# S7CAS-PLEIADES-CARTE-MERE_P01_IO.net
KiCad netlist of a schematic drawn in Altium Designer
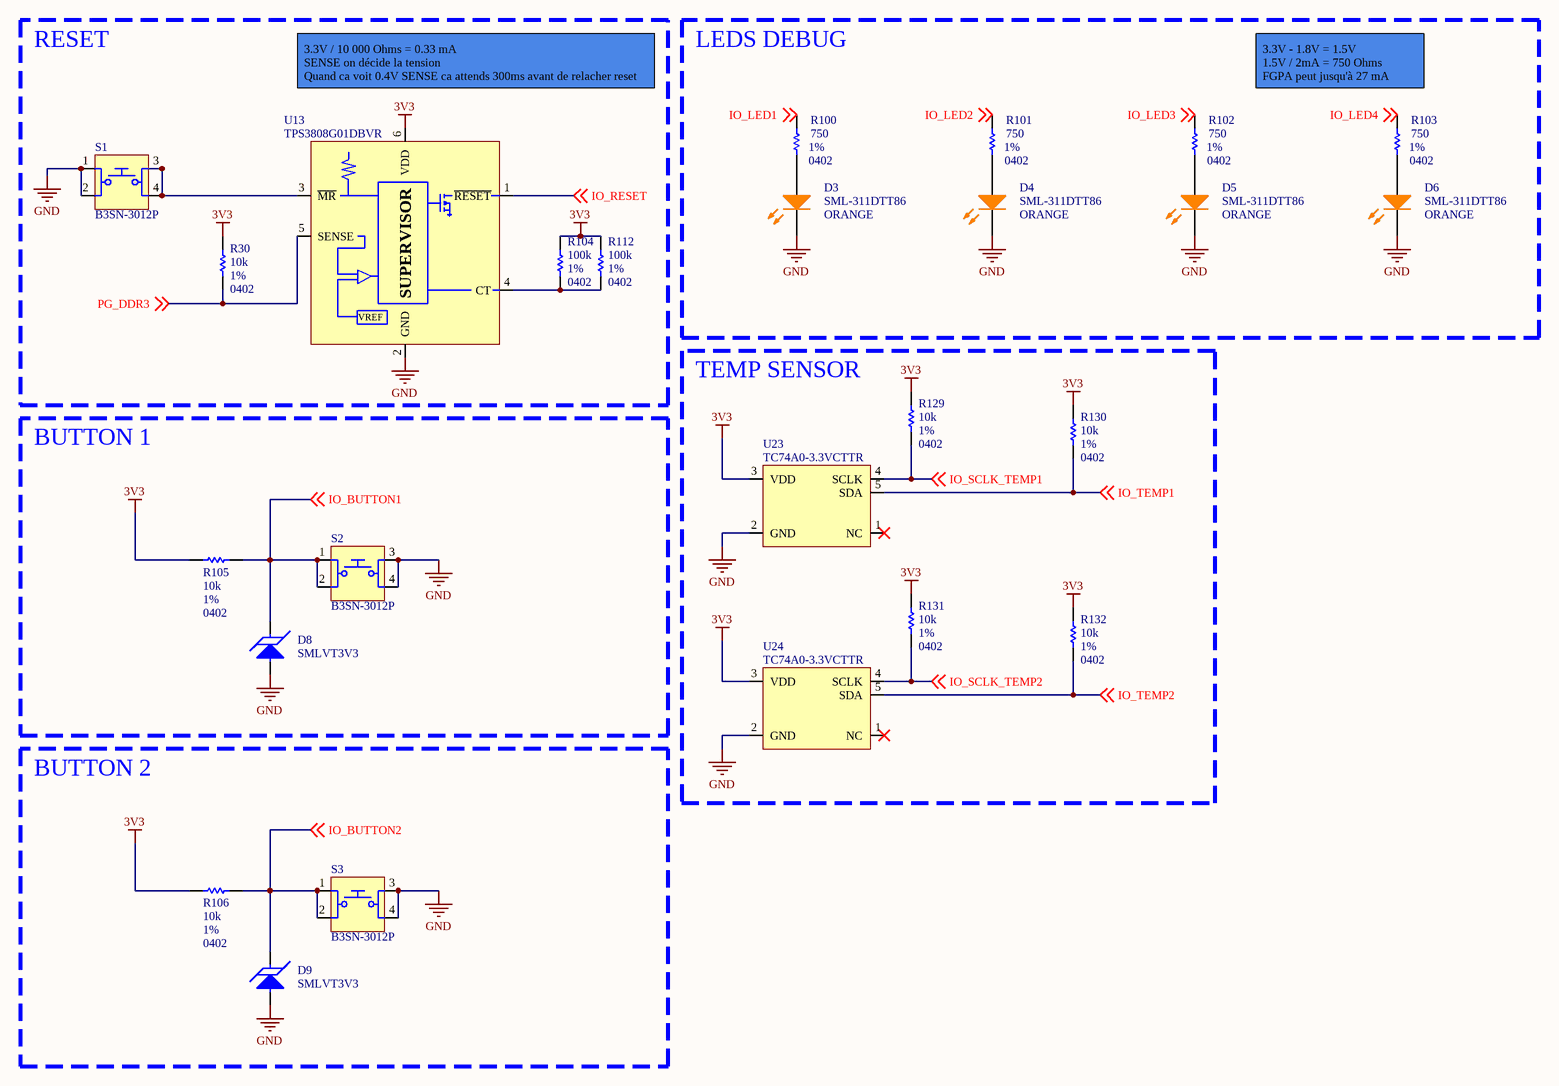
[diagram p0: S7CAS-PLEIADES-CARTE-MERE_P01_IO.SchDoc]

(export (version "E")
  (design (tool "Eeschema 10.0.6"))
  (components
    (comp (ref "D3")
      (value "SML-311DTT86")
      (footprint "LED_0603")
      (description "LED - 611nM ORANGE 2mA - 0603")
      (fields
        (field (name "VOLTAGE") "1.8V")
        (field (name "MFG") "ROHM Semiconductor")
        (field (name "ALTIUM_VALUE") "ORANGE")
        (field (name "CREATEDBY") "Jonathan Bouchard")
      )
      (libsource (lib "s7cas_lib2023") (part "LED_SML-311DTT86"))
    )
    (comp (ref "D4")
      (value "SML-311DTT86")
      (footprint "LED_0603")
      (description "LED - 611nM ORANGE 2mA - 0603")
      (fields
        (field (name "VOLTAGE") "1.8V")
        (field (name "MFG") "ROHM Semiconductor")
        (field (name "ALTIUM_VALUE") "ORANGE")
        (field (name "CREATEDBY") "Jonathan Bouchard")
      )
      (libsource (lib "s7cas_lib2023") (part "LED_SML-311DTT86"))
    )
    (comp (ref "D5")
      (value "SML-311DTT86")
      (footprint "LED_0603")
      (description "LED - 611nM ORANGE 2mA - 0603")
      (fields
        (field (name "VOLTAGE") "1.8V")
        (field (name "MFG") "ROHM Semiconductor")
        (field (name "ALTIUM_VALUE") "ORANGE")
        (field (name "CREATEDBY") "Jonathan Bouchard")
      )
      (libsource (lib "s7cas_lib2023") (part "LED_SML-311DTT86"))
    )
    (comp (ref "D6")
      (value "SML-311DTT86")
      (footprint "LED_0603")
      (description "LED - 611nM ORANGE 2mA - 0603")
      (fields
        (field (name "VOLTAGE") "1.8V")
        (field (name "MFG") "ROHM Semiconductor")
        (field (name "ALTIUM_VALUE") "ORANGE")
        (field (name "CREATEDBY") "Jonathan Bouchard")
      )
      (libsource (lib "s7cas_lib2023") (part "LED_SML-311DTT86"))
    )
    (comp (ref "D8")
      (value "SMLVT3V3")
      (footprint "TVS_POW_SMLVT3V3")
      (description "TVS - 3.3V 10.3V 600W - DO214AA")
      (fields
        (field (name "CREATEDBY/DATE") "Jonathan Bouchard - 2019-04-27")
        (field (name "VERIFIEDBY") "Nicolas V. (2019-05-06)")
      )
      (libsource (lib "s7cas_lib2023") (part "TVS_POW_SMLVT3V3"))
    )
    (comp (ref "D9")
      (value "SMLVT3V3")
      (footprint "TVS_POW_SMLVT3V3")
      (description "TVS - 3.3V 10.3V 600W - DO214AA")
      (fields
        (field (name "CREATEDBY/DATE") "Jonathan Bouchard - 2019-04-27")
        (field (name "VERIFIEDBY") "Nicolas V. (2019-05-06)")
      )
      (libsource (lib "s7cas_lib2023") (part "TVS_POW_SMLVT3V3"))
    )
    (comp (ref "R30")
      (value "10k")
      (footprint "RES_0402")
      (description "10 kOhms ±1% 0.063W, 1/16W Chip Resistor 0402 (1005 Metric) Automotive AEC-Q200 Thick Film")
      (fields
        (field (name "VOLTAGE") "75V")
        (field (name "MFG PART NUMBER") "RMCF0402FT10K0")
        (field (name "PACKAGE") "0402")
        (field (name "PRECISION") "1%")
        (field (name "CREATEDBY") "Jonathan Bouchard")
      )
      (libsource (lib "s7cas_lib2023") (part "RES - 0402"))
    )
    (comp (ref "R100")
      (value "750")
      (footprint "RES_0402")
      (description "750 Ohms ±0.1% 0.063W, 1/16W Chip Resistor 0402 (1005 Metric) Automotive AEC-Q200 Thin Film")
      (fields
        (field (name "VOLTAGE") "50V")
        (field (name "MFG") "Panasonic Electronic Components")
        (field (name "PACKAGE") "0402")
        (field (name "PRECISION") "1%")
        (field (name "CREATEDBY") "Jonathan Bouchard")
      )
      (libsource (lib "s7cas_lib2023") (part "RES - 0402"))
    )
    (comp (ref "R101")
      (value "750")
      (footprint "RES_0402")
      (description "750 Ohms ±0.1% 0.063W, 1/16W Chip Resistor 0402 (1005 Metric) Automotive AEC-Q200 Thin Film")
      (fields
        (field (name "VOLTAGE") "50V")
        (field (name "MFG") "Panasonic Electronic Components")
        (field (name "PACKAGE") "0402")
        (field (name "PRECISION") "1%")
        (field (name "CREATEDBY") "Jonathan Bouchard")
      )
      (libsource (lib "s7cas_lib2023") (part "RES - 0402"))
    )
    (comp (ref "R102")
      (value "750")
      (footprint "RES_0402")
      (description "750 Ohms ±0.1% 0.063W, 1/16W Chip Resistor 0402 (1005 Metric) Automotive AEC-Q200 Thin Film")
      (fields
        (field (name "VOLTAGE") "50V")
        (field (name "MFG") "Panasonic Electronic Components")
        (field (name "PACKAGE") "0402")
        (field (name "PRECISION") "1%")
        (field (name "CREATEDBY") "Jonathan Bouchard")
      )
      (libsource (lib "s7cas_lib2023") (part "RES - 0402"))
    )
    (comp (ref "R103")
      (value "750")
      (footprint "RES_0402")
      (description "750 Ohms ±0.1% 0.063W, 1/16W Chip Resistor 0402 (1005 Metric) Automotive AEC-Q200 Thin Film")
      (fields
        (field (name "VOLTAGE") "50V")
        (field (name "MFG") "Panasonic Electronic Components")
        (field (name "PACKAGE") "0402")
        (field (name "PRECISION") "1%")
        (field (name "CREATEDBY") "Jonathan Bouchard")
      )
      (libsource (lib "s7cas_lib2023") (part "RES - 0402"))
    )
    (comp (ref "R104")
      (value "100k")
      (footprint "RES_0402")
      (description "100 kOhms ±1% 0.063W, 1/16W Chip Resistor 0402 (1005 Metric) Moisture Resistant Thick Film")
      (fields
        (field (name "VOLTAGE") "75V")
        (field (name "MFG PART NUMBER") "RC0402FR-07100KL")
        (field (name "PACKAGE") "0402")
        (field (name "PRECISION") "1%")
        (field (name "CREATEDBY") "Jonathan Bouchard")
      )
      (libsource (lib "s7cas_lib2023") (part "RES - 0402"))
    )
    (comp (ref "R105")
      (value "10k")
      (footprint "RES_0402")
      (description "10 kOhms ±1% 0.063W, 1/16W Chip Resistor 0402 (1005 Metric) Automotive AEC-Q200 Thick Film")
      (fields
        (field (name "VOLTAGE") "75V")
        (field (name "MFG PART NUMBER") "RMCF0402FT10K0")
        (field (name "PACKAGE") "0402")
        (field (name "PRECISION") "1%")
        (field (name "CREATEDBY") "Jonathan Bouchard")
      )
      (libsource (lib "s7cas_lib2023") (part "RES - 0402"))
    )
    (comp (ref "R106")
      (value "10k")
      (footprint "RES_0402")
      (description "10 kOhms ±1% 0.063W, 1/16W Chip Resistor 0402 (1005 Metric) Automotive AEC-Q200 Thick Film")
      (fields
        (field (name "VOLTAGE") "75V")
        (field (name "MFG PART NUMBER") "RMCF0402FT10K0")
        (field (name "PACKAGE") "0402")
        (field (name "PRECISION") "1%")
        (field (name "CREATEDBY") "Jonathan Bouchard")
      )
      (libsource (lib "s7cas_lib2023") (part "RES - 0402"))
    )
    (comp (ref "R112")
      (value "100k")
      (footprint "RES_0402")
      (description "100 kOhms ±1% 0.063W, 1/16W Chip Resistor 0402 (1005 Metric) Moisture Resistant Thick Film")
      (fields
        (field (name "VOLTAGE") "75V")
        (field (name "MFG PART NUMBER") "RC0402FR-07100KL")
        (field (name "PACKAGE") "0402")
        (field (name "PRECISION") "1%")
        (field (name "CREATEDBY") "Jonathan Bouchard")
      )
      (libsource (lib "s7cas_lib2023") (part "RES - 0402"))
    )
    (comp (ref "R129")
      (value "10k")
      (footprint "RES_0402")
      (description "10 kOhms ±1% 0.063W, 1/16W Chip Resistor 0402 (1005 Metric) Automotive AEC-Q200 Thick Film")
      (fields
        (field (name "VOLTAGE") "75V")
        (field (name "MFG PART NUMBER") "RMCF0402FT10K0")
        (field (name "PACKAGE") "0402")
        (field (name "PRECISION") "1%")
        (field (name "CREATEDBY") "Jonathan Bouchard")
      )
      (libsource (lib "s7cas_lib2023") (part "RES - 0402"))
    )
    (comp (ref "R130")
      (value "10k")
      (footprint "RES_0402")
      (description "10 kOhms ±1% 0.063W, 1/16W Chip Resistor 0402 (1005 Metric) Automotive AEC-Q200 Thick Film")
      (fields
        (field (name "VOLTAGE") "75V")
        (field (name "MFG PART NUMBER") "RMCF0402FT10K0")
        (field (name "PACKAGE") "0402")
        (field (name "PRECISION") "1%")
        (field (name "CREATEDBY") "Jonathan Bouchard")
      )
      (libsource (lib "s7cas_lib2023") (part "RES - 0402"))
    )
    (comp (ref "R131")
      (value "10k")
      (footprint "RES_0402")
      (description "10 kOhms ±1% 0.063W, 1/16W Chip Resistor 0402 (1005 Metric) Automotive AEC-Q200 Thick Film")
      (fields
        (field (name "VOLTAGE") "75V")
        (field (name "MFG PART NUMBER") "RMCF0402FT10K0")
        (field (name "PACKAGE") "0402")
        (field (name "PRECISION") "1%")
        (field (name "CREATEDBY") "Jonathan Bouchard")
      )
      (libsource (lib "s7cas_lib2023") (part "RES - 0402"))
    )
    (comp (ref "R132")
      (value "10k")
      (footprint "RES_0402")
      (description "10 kOhms ±1% 0.063W, 1/16W Chip Resistor 0402 (1005 Metric) Automotive AEC-Q200 Thick Film")
      (fields
        (field (name "VOLTAGE") "75V")
        (field (name "MFG PART NUMBER") "RMCF0402FT10K0")
        (field (name "PACKAGE") "0402")
        (field (name "PRECISION") "1%")
        (field (name "CREATEDBY") "Jonathan Bouchard")
      )
      (libsource (lib "s7cas_lib2023") (part "RES - 0402"))
    )
    (comp (ref "S1")
      (value "B3SN-3012P")
      (footprint "SWI_TACT_B3SN-3012P")
      (description "SWI - SWITCH TACTILE SPST-NO 0.05A 24V -SMD")
      (fields
        (field (name "CREATEDBY/DATE") "Olivier Bernard / 5/12/2017")
        (field (name "VERIFIEDBY") "Caroline Paulin / 11 juillet 2018")
      )
      (libsource (lib "s7cas_lib2023") (part "SWI_TACT_B3SN-3012P_1"))
    )
    (comp (ref "S2")
      (value "B3SN-3012P")
      (footprint "SWI_TACT_B3SN-3012P")
      (description "SWI - SWITCH TACTILE SPST-NO 0.05A 24V -SMD")
      (fields
        (field (name "CREATEDBY/DATE") "Olivier Bernard / 5/12/2017")
        (field (name "VERIFIEDBY") "Caroline Paulin / 11 juillet 2018")
      )
      (libsource (lib "s7cas_lib2023") (part "SWI_TACT_B3SN-3012P_1"))
    )
    (comp (ref "S3")
      (value "B3SN-3012P")
      (footprint "SWI_TACT_B3SN-3012P")
      (description "SWI - SWITCH TACTILE SPST-NO 0.05A 24V -SMD")
      (fields
        (field (name "CREATEDBY/DATE") "Olivier Bernard / 5/12/2017")
        (field (name "VERIFIEDBY") "Caroline Paulin / 11 juillet 2018")
      )
      (libsource (lib "s7cas_lib2023") (part "SWI_TACT_B3SN-3012P_1"))
    )
    (comp (ref "U13")
      (value "TPS3808G01DBVR")
      (footprint "POW_RESET_TPS3808")
      (description "POW - VOLT SUPERVISOR ADJ - SOT23-6")
      (fields (field (name "MFG") "Texas Instruments") (field (name "CREATEDBY") "Jonathan Bouchard"))
      (libsource (lib "s7cas_lib2023") (part "POW_RESET_TPS3808G01DBVR"))
    )
    (comp (ref "U23")
      (value "TC74A0-3.3VCTTR")
      (footprint "SEN_TEMP_TC74A0-3.3VCTTR")
      (description "SENS - TEMPERATURE SENSOR I2C/SMBUS - SOT23-5")
      (fields
        (field (name "VOLTAGE") "2.7 V ~ 5.5 V")
        (field (name "MFG") "Microchip")
        (field (name "CREATEDBY") "Jonathan Bouchard")
      )
      (libsource (lib "s7cas_lib2023") (part "SENS_TEMP_TC74A0-3.3VCTTR"))
    )
    (comp (ref "U24")
      (value "TC74A0-3.3VCTTR")
      (footprint "SEN_TEMP_TC74A0-3.3VCTTR")
      (description "SENS - TEMPERATURE SENSOR I2C/SMBUS - SOT23-5")
      (fields
        (field (name "VOLTAGE") "2.7 V ~ 5.5 V")
        (field (name "MFG") "Microchip")
        (field (name "CREATEDBY") "Jonathan Bouchard")
      )
      (libsource (lib "s7cas_lib2023") (part "SENS_TEMP_TC74A0-3.3VCTTR"))
    )
  )
  (nets
    (net (code "1") (name "3V3") (class "Default")
      (node (ref "R104") (pin "2") (pinfunction "2_2") (pintype "passive"))
      (node (ref "R105") (pin "1") (pinfunction "1_1") (pintype "passive"))
      (node (ref "R106") (pin "1") (pinfunction "1_1") (pintype "passive"))
      (node (ref "R112") (pin "2") (pinfunction "2_2") (pintype "passive"))
      (node (ref "R129") (pin "2") (pinfunction "2_2") (pintype "passive"))
      (node (ref "R130") (pin "2") (pinfunction "2_2") (pintype "passive"))
      (node (ref "R131") (pin "2") (pinfunction "2_2") (pintype "passive"))
      (node (ref "R132") (pin "2") (pinfunction "2_2") (pintype "passive"))
      (node (ref "R30") (pin "2") (pinfunction "2_2") (pintype "passive"))
      (node (ref "U13") (pin "6") (pinfunction "VDD_6") (pintype "power_in"))
      (node (ref "U23") (pin "3") (pinfunction "VDD_3") (pintype "passive"))
      (node (ref "U24") (pin "3") (pinfunction "VDD_3") (pintype "passive"))
    )
    (net (code "2") (name "GND") (class "Default")
      (node (ref "D3") (pin "K") (pinfunction "K_K") (pintype "passive"))
      (node (ref "D4") (pin "K") (pinfunction "K_K") (pintype "passive"))
      (node (ref "D5") (pin "K") (pinfunction "K_K") (pintype "passive"))
      (node (ref "D6") (pin "K") (pinfunction "K_K") (pintype "passive"))
      (node (ref "D8") (pin "A") (pinfunction "A_A") (pintype "passive"))
      (node (ref "D9") (pin "A") (pinfunction "A_A") (pintype "passive"))
      (node (ref "S1") (pin "1") (pinfunction "1_1") (pintype "passive"))
      (node (ref "S1") (pin "2") (pinfunction "2_2") (pintype "passive"))
      (node (ref "S2") (pin "3") (pinfunction "3_3") (pintype "passive"))
      (node (ref "S2") (pin "4") (pinfunction "4_4") (pintype "passive"))
      (node (ref "S3") (pin "3") (pinfunction "3_3") (pintype "passive"))
      (node (ref "S3") (pin "4") (pinfunction "4_4") (pintype "passive"))
      (node (ref "U13") (pin "2") (pinfunction "GND_2") (pintype "passive"))
      (node (ref "U23") (pin "2") (pinfunction "GND_2") (pintype "passive"))
      (node (ref "U24") (pin "2") (pinfunction "GND_2") (pintype "passive"))
    )
    (net (code "3") (name "IO_BUTTON1") (class "Default")
      (node (ref "D8") (pin "K") (pinfunction "K_K") (pintype "passive"))
      (node (ref "R105") (pin "2") (pinfunction "2_2") (pintype "passive"))
      (node (ref "S2") (pin "1") (pinfunction "1_1") (pintype "passive"))
      (node (ref "S2") (pin "2") (pinfunction "2_2") (pintype "passive"))
    )
    (net (code "4") (name "IO_BUTTON2") (class "Default")
      (node (ref "D9") (pin "K") (pinfunction "K_K") (pintype "passive"))
      (node (ref "R106") (pin "2") (pinfunction "2_2") (pintype "passive"))
      (node (ref "S3") (pin "1") (pinfunction "1_1") (pintype "passive"))
      (node (ref "S3") (pin "2") (pinfunction "2_2") (pintype "passive"))
    )
    (net (code "5") (name "IO_LED1") (class "Default")
      (node (ref "R100") (pin "2") (pinfunction "2_2") (pintype "passive"))
    )
    (net (code "6") (name "IO_LED2") (class "Default")
      (node (ref "R101") (pin "2") (pinfunction "2_2") (pintype "passive"))
    )
    (net (code "7") (name "IO_LED3") (class "Default")
      (node (ref "R102") (pin "2") (pinfunction "2_2") (pintype "passive"))
    )
    (net (code "8") (name "IO_LED4") (class "Default")
      (node (ref "R103") (pin "2") (pinfunction "2_2") (pintype "passive"))
    )
    (net (code "9") (name "IO_RESET") (class "Default")
      (node (ref "U13") (pin "1") (pinfunction "RESET_1") (pintype "passive"))
    )
    (net (code "10") (name "IO_SCLK_TEMP1") (class "Default")
      (node (ref "R129") (pin "1") (pinfunction "1_1") (pintype "passive"))
      (node (ref "U23") (pin "4") (pinfunction "SCLK_4") (pintype "passive"))
    )
    (net (code "11") (name "IO_SCLK_TEMP2") (class "Default")
      (node (ref "R131") (pin "1") (pinfunction "1_1") (pintype "passive"))
      (node (ref "U24") (pin "4") (pinfunction "SCLK_4") (pintype "passive"))
    )
    (net (code "12") (name "IO_TEMP1") (class "Default")
      (node (ref "R130") (pin "1") (pinfunction "1_1") (pintype "passive"))
      (node (ref "U23") (pin "5") (pinfunction "SDA_5") (pintype "passive"))
    )
    (net (code "13") (name "IO_TEMP2") (class "Default")
      (node (ref "R132") (pin "1") (pinfunction "1_1") (pintype "passive"))
      (node (ref "U24") (pin "5") (pinfunction "SDA_5") (pintype "passive"))
    )
    (net (code "14") (name "Net-(D3-PadA)") (class "Default")
      (node (ref "D3") (pin "A") (pinfunction "A_A") (pintype "passive"))
      (node (ref "R100") (pin "1") (pinfunction "1_1") (pintype "passive"))
    )
    (net (code "15") (name "Net-(D4-PadA)") (class "Default")
      (node (ref "D4") (pin "A") (pinfunction "A_A") (pintype "passive"))
      (node (ref "R101") (pin "1") (pinfunction "1_1") (pintype "passive"))
    )
    (net (code "16") (name "Net-(D5-PadA)") (class "Default")
      (node (ref "D5") (pin "A") (pinfunction "A_A") (pintype "passive"))
      (node (ref "R102") (pin "1") (pinfunction "1_1") (pintype "passive"))
    )
    (net (code "17") (name "Net-(D6-PadA)") (class "Default")
      (node (ref "D6") (pin "A") (pinfunction "A_A") (pintype "passive"))
      (node (ref "R103") (pin "1") (pinfunction "1_1") (pintype "passive"))
    )
    (net (code "18") (name "Net-(U13-CT)") (class "Default")
      (node (ref "R104") (pin "1") (pinfunction "1_1") (pintype "passive"))
      (node (ref "R112") (pin "1") (pinfunction "1_1") (pintype "passive"))
      (node (ref "U13") (pin "4") (pinfunction "CT_4") (pintype "passive"))
    )
    (net (code "19") (name "Net-(U13-MR)") (class "Default")
      (node (ref "S1") (pin "3") (pinfunction "3_3") (pintype "passive"))
      (node (ref "S1") (pin "4") (pinfunction "4_4") (pintype "passive"))
      (node (ref "U13") (pin "3") (pinfunction "MR_3") (pintype "passive"))
    )
    (net (code "20") (name "PG_DDR3") (class "Default")
      (node (ref "R30") (pin "1") (pinfunction "1_1") (pintype "passive"))
      (node (ref "U13") (pin "5") (pinfunction "SENSE_5") (pintype "passive"))
    )
    (net (code "21") (name "unconnected-(U23-NC-Pad1)") (class "Default")
      (node (ref "U23") (pin "1") (pinfunction "NC_1") (pintype "passive+no_connect"))
    )
    (net (code "22") (name "unconnected-(U24-NC-Pad1)") (class "Default")
      (node (ref "U24") (pin "1") (pinfunction "NC_1") (pintype "passive+no_connect"))
    )
  )
)
